# Z-Taster.net
KiCad netlist of a schematic drawn in EAGLE
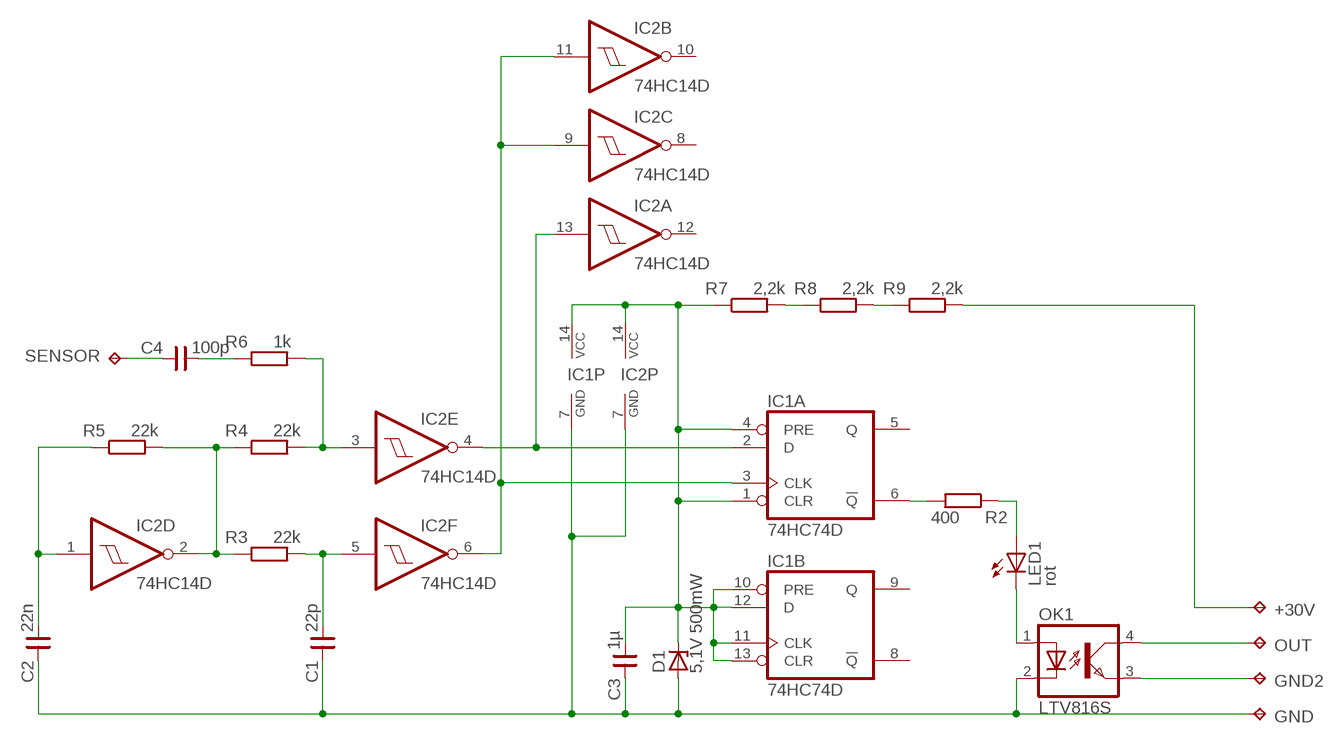
[diagram p0: schematic, sheet 1]

(export (version "E")
  (design (tool "Eeschema 10.0.6"))
  (components
    (comp (ref "+30V")
      (value "TPTP20SQ")
      (footprint "eagle-import:TP20SQ")
      (libsource (lib "eagle-import") (part "TPTP20SQ"))
    )
    (comp (ref "C1")
      (value "22p")
      (footprint "eagle-import:R0805")
      (libsource (lib "eagle-import") (part "C0805"))
    )
    (comp (ref "C2")
      (value "22n")
      (footprint "eagle-import:R0805")
      (libsource (lib "eagle-import") (part "C0805"))
    )
    (comp (ref "C3")
      (value "1µ")
      (footprint "eagle-import:R0805")
      (libsource (lib "eagle-import") (part "C0805"))
    )
    (comp (ref "C4")
      (value "100p")
      (footprint "eagle-import:R0805")
      (libsource (lib "eagle-import") (part "C0805"))
    )
    (comp (ref "D1")
      (value "5,1V 500mW")
      (footprint "eagle-import:SOD80C")
      (libsource (lib "eagle-import") (part "ZENER-DIODESOD80C"))
    )
    (comp (ref "GND")
      (value "TPTP18SQ")
      (footprint "eagle-import:TP18SQ")
      (libsource (lib "eagle-import") (part "TPTP18SQ"))
    )
    (comp (ref "GND2")
      (value "TPTP18SQ")
      (footprint "eagle-import:TP18SQ")
      (libsource (lib "eagle-import") (part "TPTP18SQ"))
    )
    (comp (ref "IC1")
      (value "74HC74D")
      (footprint "eagle-import:SO14")
      (libsource (lib "eagle-import") (part "7474DHC"))
    )
    (comp (ref "IC2")
      (value "74HC14D")
      (footprint "eagle-import:SO14")
      (libsource (lib "eagle-import") (part "7414DHC"))
    )
    (comp (ref "LED1")
      (value "rot")
      (footprint "eagle-import:LED0805")
      (libsource (lib "eagle-import") (part "LED0805"))
    )
    (comp (ref "OK1")
      (value "LTV816S")
      (footprint "eagle-import:SMD4")
      (libsource (lib "eagle-import") (part "LTV816S"))
    )
    (comp (ref "OUT")
      (value "TPTP18SQ")
      (footprint "eagle-import:TP18SQ")
      (libsource (lib "eagle-import") (part "TPTP18SQ"))
    )
    (comp (ref "R2")
      (value "400")
      (footprint "eagle-import:R0805")
      (libsource (lib "eagle-import") (part "R805"))
    )
    (comp (ref "R3")
      (value "22k")
      (footprint "eagle-import:R0805")
      (libsource (lib "eagle-import") (part "R805"))
    )
    (comp (ref "R4")
      (value "22k")
      (footprint "eagle-import:R0805")
      (libsource (lib "eagle-import") (part "R805"))
    )
    (comp (ref "R5")
      (value "22k")
      (footprint "eagle-import:R0805")
      (libsource (lib "eagle-import") (part "R805"))
    )
    (comp (ref "R6")
      (value "1k")
      (footprint "eagle-import:R0805")
      (libsource (lib "eagle-import") (part "R805"))
    )
    (comp (ref "R7")
      (value "2,2k")
      (footprint "eagle-import:R0805")
      (libsource (lib "eagle-import") (part "R805"))
    )
    (comp (ref "R8")
      (value "2,2k")
      (footprint "eagle-import:R0805")
      (libsource (lib "eagle-import") (part "R805"))
    )
    (comp (ref "R9")
      (value "2,2k")
      (footprint "eagle-import:R0805")
      (libsource (lib "eagle-import") (part "R805"))
    )
    (comp (ref "SENSOR")
      (value "TPTP18SQ")
      (footprint "eagle-import:TP18SQ")
      (libsource (lib "eagle-import") (part "TPTP18SQ"))
    )
  )
  (nets
    (net (code "1") (name "Net-(+30V-PadTP)") (class "Default")
      (node (ref "+30V") (pin "TP") (pinfunction "TP_TP") (pintype "input"))
      (node (ref "R9") (pin "2") (pinfunction "2_2") (pintype "passive"))
    )
    (net (code "2") (name "Net-(C4-Pad1)") (class "Default")
      (node (ref "C4") (pin "1") (pinfunction "1_1") (pintype "passive"))
      (node (ref "SENSOR") (pin "TP") (pinfunction "TP_TP") (pintype "input"))
    )
    (net (code "3") (name "Net-(C4-Pad2)") (class "Default")
      (node (ref "C4") (pin "2") (pinfunction "2_2") (pintype "passive"))
      (node (ref "R6") (pin "1") (pinfunction "1_1") (pintype "passive"))
    )
    (net (code "4") (name "Net-(IC1A-CLK)") (class "Default")
      (node (ref "IC1") (pin "3") (pinfunction "CLK_3") (pintype "input"))
      (node (ref "IC2") (pin "11") (pinfunction "I_11") (pintype "input"))
      (node (ref "IC2") (pin "6") (pinfunction "O_6") (pintype "output"))
      (node (ref "IC2") (pin "9") (pinfunction "I_9") (pintype "input"))
    )
    (net (code "5") (name "Net-(IC1A-CLR)") (class "Default")
      (node (ref "C3") (pin "2") (pinfunction "2_2") (pintype "passive"))
      (node (ref "D1") (pin "C") (pinfunction "C_C") (pintype "passive"))
      (node (ref "IC1") (pin "1") (pinfunction "CLR_1") (pintype "input"))
      (node (ref "IC1") (pin "10") (pinfunction "PRE_10") (pintype "input"))
      (node (ref "IC1") (pin "11") (pinfunction "CLK_11") (pintype "input"))
      (node (ref "IC1") (pin "12") (pinfunction "D_12") (pintype "input"))
      (node (ref "IC1") (pin "13") (pinfunction "CLR_13") (pintype "input"))
      (node (ref "IC1") (pin "14") (pinfunction "VCC_14") (pintype "power_in"))
      (node (ref "IC1") (pin "4") (pinfunction "PRE_4") (pintype "input"))
      (node (ref "IC2") (pin "14") (pinfunction "VCC_14") (pintype "power_in"))
      (node (ref "R7") (pin "1") (pinfunction "1_1") (pintype "passive"))
    )
    (net (code "6") (name "Net-(IC1A-D)") (class "Default")
      (node (ref "IC1") (pin "2") (pinfunction "D_2") (pintype "input"))
      (node (ref "IC2") (pin "13") (pinfunction "I_13") (pintype "input"))
      (node (ref "IC2") (pin "4") (pinfunction "O_4") (pintype "output"))
    )
    (net (code "7") (name "Net-(IC1A-~{Q})") (class "Default")
      (node (ref "IC1") (pin "6") (pinfunction "~{Q}_6") (pintype "output"))
      (node (ref "R2") (pin "2") (pinfunction "2_2") (pintype "passive"))
    )
    (net (code "8") (name "Net-(IC1C-GND)") (class "Default")
      (node (ref "C1") (pin "1") (pinfunction "1_1") (pintype "passive"))
      (node (ref "C2") (pin "1") (pinfunction "1_1") (pintype "passive"))
      (node (ref "C3") (pin "1") (pinfunction "1_1") (pintype "passive"))
      (node (ref "D1") (pin "A") (pinfunction "A_A") (pintype "passive"))
      (node (ref "GND") (pin "TP") (pinfunction "TP_TP") (pintype "input"))
      (node (ref "IC1") (pin "7") (pinfunction "GND_7") (pintype "power_in"))
      (node (ref "IC2") (pin "7") (pinfunction "GND_7") (pintype "power_in"))
      (node (ref "OK1") (pin "2") (pinfunction "C_2") (pintype "passive"))
    )
    (net (code "9") (name "Net-(IC2D-I)") (class "Default")
      (node (ref "C2") (pin "2") (pinfunction "2_2") (pintype "passive"))
      (node (ref "IC2") (pin "1") (pinfunction "I_1") (pintype "input"))
      (node (ref "R5") (pin "1") (pinfunction "1_1") (pintype "passive"))
    )
    (net (code "10") (name "Net-(IC2D-O)") (class "Default")
      (node (ref "IC2") (pin "2") (pinfunction "O_2") (pintype "output"))
      (node (ref "R3") (pin "1") (pinfunction "1_1") (pintype "passive"))
      (node (ref "R4") (pin "1") (pinfunction "1_1") (pintype "passive"))
      (node (ref "R5") (pin "2") (pinfunction "2_2") (pintype "passive"))
    )
    (net (code "11") (name "Net-(IC2E-I)") (class "Default")
      (node (ref "IC2") (pin "3") (pinfunction "I_3") (pintype "input"))
      (node (ref "R4") (pin "2") (pinfunction "2_2") (pintype "passive"))
      (node (ref "R6") (pin "2") (pinfunction "2_2") (pintype "passive"))
    )
    (net (code "12") (name "Net-(IC2F-I)") (class "Default")
      (node (ref "C1") (pin "2") (pinfunction "2_2") (pintype "passive"))
      (node (ref "IC2") (pin "5") (pinfunction "I_5") (pintype "input"))
      (node (ref "R3") (pin "2") (pinfunction "2_2") (pintype "passive"))
    )
    (net (code "13") (name "Net-(LED1-PadA)") (class "Default")
      (node (ref "LED1") (pin "A") (pinfunction "A_A") (pintype "passive"))
      (node (ref "R2") (pin "1") (pinfunction "1_1") (pintype "passive"))
    )
    (net (code "14") (name "Net-(OK1-A)") (class "Default")
      (node (ref "LED1") (pin "C") (pinfunction "C_C") (pintype "passive"))
      (node (ref "OK1") (pin "1") (pinfunction "A_1") (pintype "passive"))
    )
    (net (code "15") (name "Net-(OK1-COL)") (class "Default")
      (node (ref "OK1") (pin "4") (pinfunction "COL_4") (pintype "passive"))
      (node (ref "OUT") (pin "TP") (pinfunction "TP_TP") (pintype "input"))
    )
    (net (code "16") (name "Net-(OK1-EMIT)") (class "Default")
      (node (ref "GND2") (pin "TP") (pinfunction "TP_TP") (pintype "input"))
      (node (ref "OK1") (pin "3") (pinfunction "EMIT_3") (pintype "passive"))
    )
    (net (code "17") (name "Net-(R7-Pad2)") (class "Default")
      (node (ref "R7") (pin "2") (pinfunction "2_2") (pintype "passive"))
      (node (ref "R8") (pin "1") (pinfunction "1_1") (pintype "passive"))
    )
    (net (code "18") (name "Net-(R8-Pad2)") (class "Default")
      (node (ref "R8") (pin "2") (pinfunction "2_2") (pintype "passive"))
      (node (ref "R9") (pin "1") (pinfunction "1_1") (pintype "passive"))
    )
    (net (code "19") (name "unconnected-(IC1A-Q-Pad5)") (class "Default")
      (node (ref "IC1") (pin "5") (pinfunction "Q_5") (pintype "output"))
    )
    (net (code "20") (name "unconnected-(IC1B-Q-Pad9)") (class "Default")
      (node (ref "IC1") (pin "9") (pinfunction "Q_9") (pintype "output"))
    )
    (net (code "21") (name "unconnected-(IC1B-~{Q}-Pad8)") (class "Default")
      (node (ref "IC1") (pin "8") (pinfunction "~{Q}_8") (pintype "output"))
    )
    (net (code "22") (name "unconnected-(IC2A-O-Pad12)") (class "Default")
      (node (ref "IC2") (pin "12") (pinfunction "O_12") (pintype "output"))
    )
    (net (code "23") (name "unconnected-(IC2B-O-Pad10)") (class "Default")
      (node (ref "IC2") (pin "10") (pinfunction "O_10") (pintype "output"))
    )
    (net (code "24") (name "unconnected-(IC2C-O-Pad8)") (class "Default")
      (node (ref "IC2") (pin "8") (pinfunction "O_8") (pintype "output"))
    )
  )
)
